# Arduino_keyboard_schematic.net
KiCad netlist of a schematic drawn in EAGLE
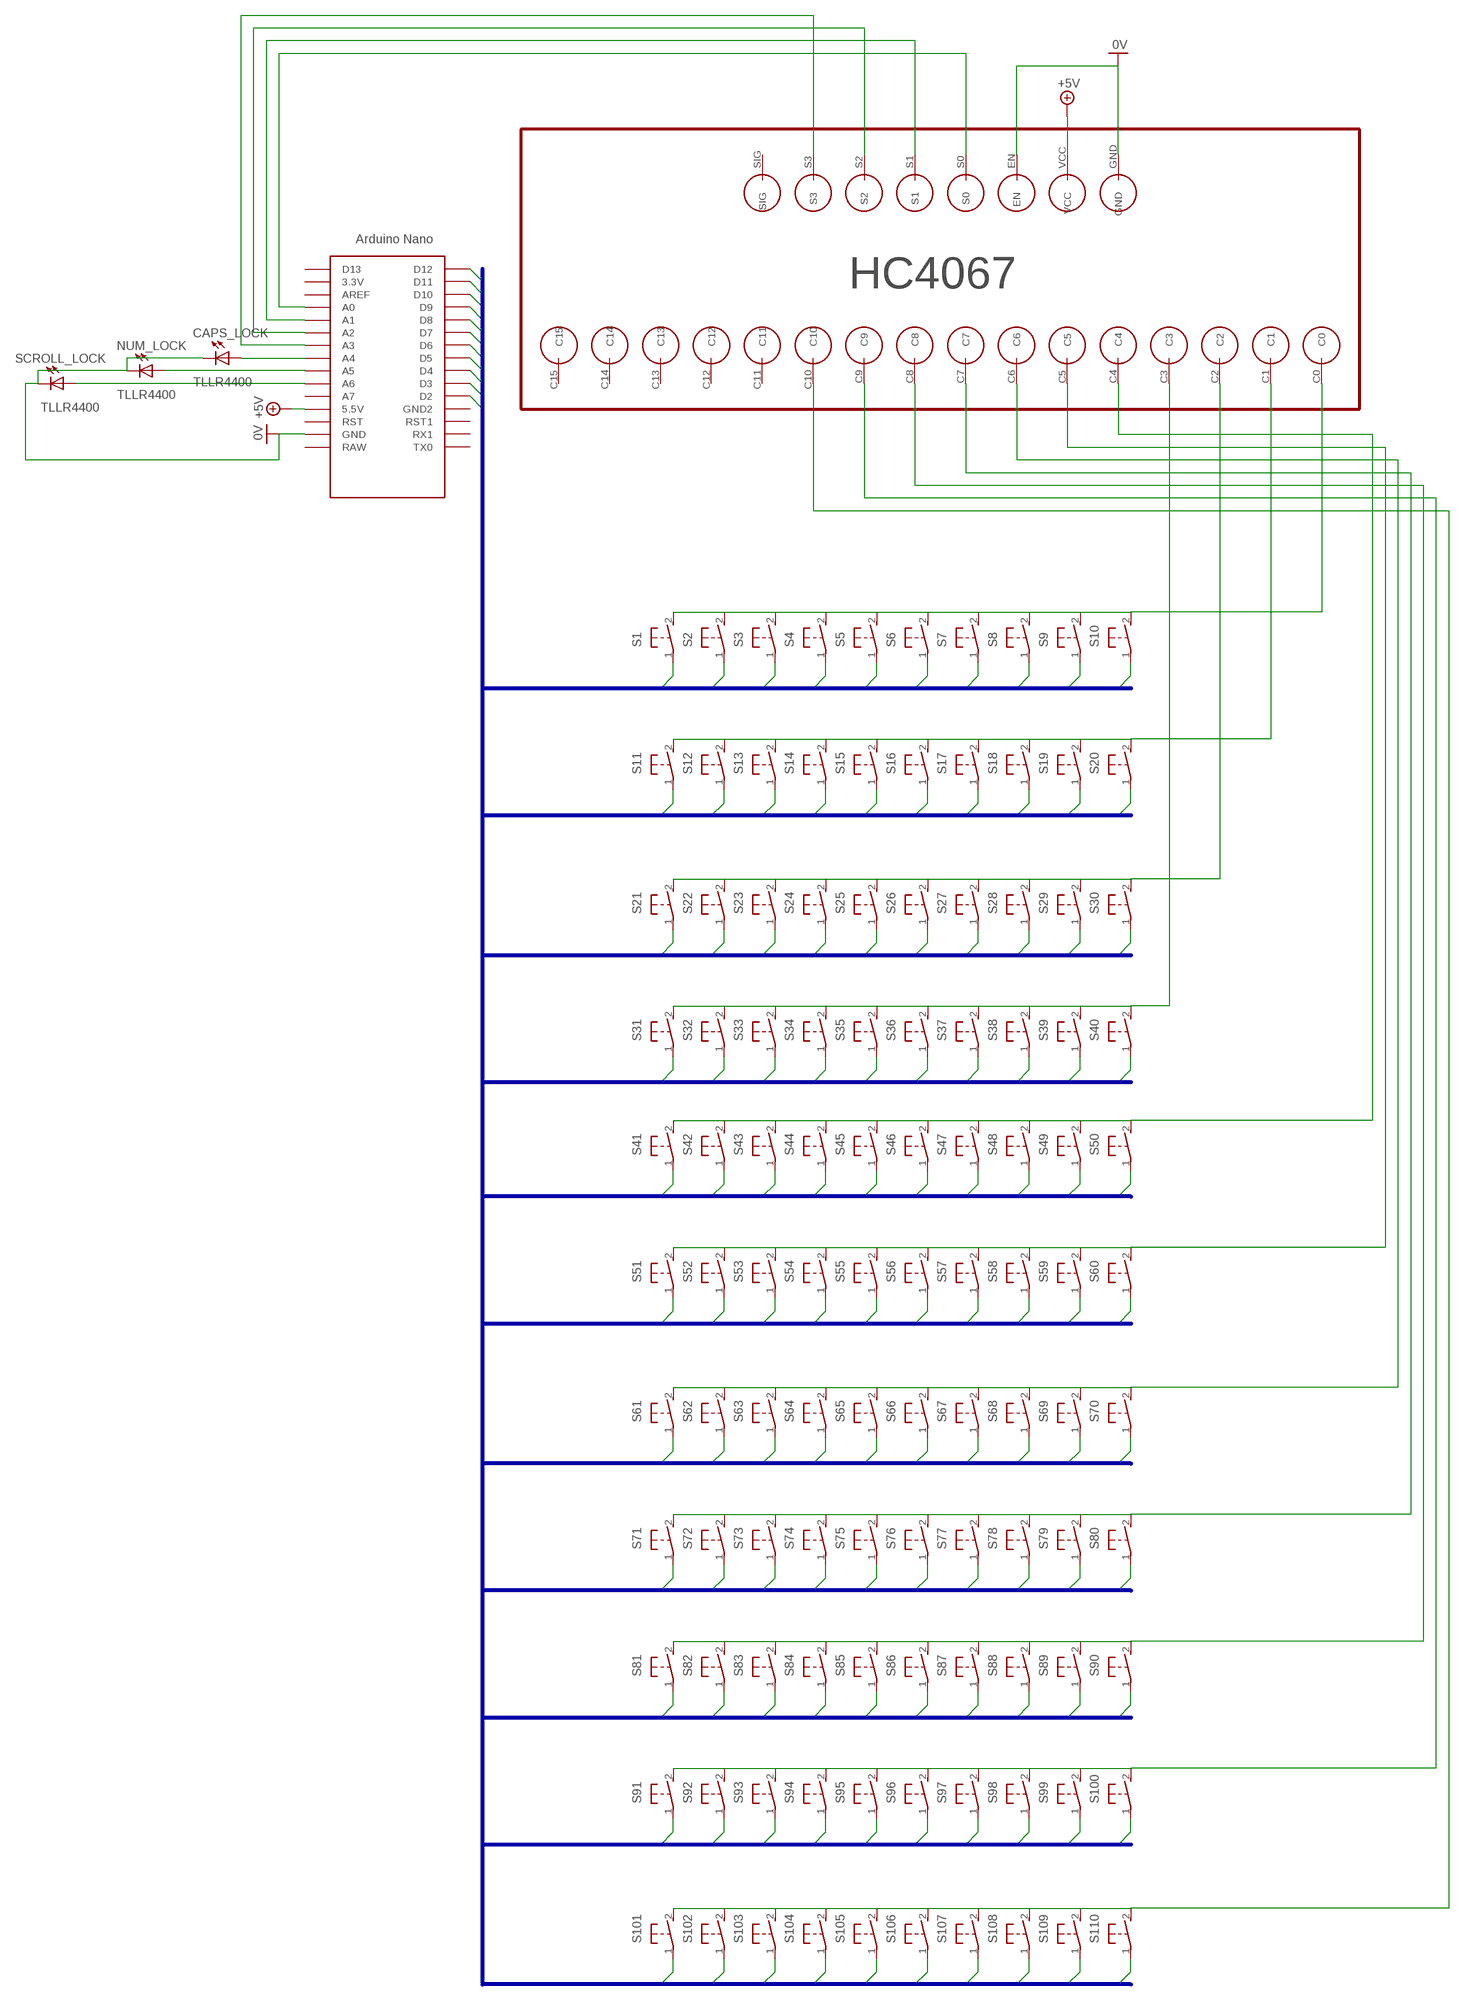
[diagram p0: schematic, sheet 1]

(export (version "E")
  (design (tool "Eeschema 10.0.6"))
  (components
    (comp (ref "CAPS_LOCK")
      (value "TLLR4400")
      (footprint "eagle-import:LED3MM")
      (fields (field (name "MF") "VISHAY SEMICONDUCTOR"))
      (libsource (lib "eagle-import") (part "TLLR4400"))
    )
    (comp (ref "NUM_LOCK")
      (value "TLLR4400")
      (footprint "eagle-import:LED3MM")
      (fields (field (name "MF") "VISHAY SEMICONDUCTOR"))
      (libsource (lib "eagle-import") (part "TLLR4400"))
    )
    (comp (ref "S1")
      (value "31-XX")
      (footprint "eagle-import:B3F-31XX")
      (fields (field (name "MPN") "B3F-3100"))
      (libsource (lib "eagle-import") (part "31-XX"))
    )
    (comp (ref "S2")
      (value "31-XX")
      (footprint "eagle-import:B3F-31XX")
      (fields (field (name "MPN") "B3F-3100"))
      (libsource (lib "eagle-import") (part "31-XX"))
    )
    (comp (ref "S3")
      (value "31-XX")
      (footprint "eagle-import:B3F-31XX")
      (fields (field (name "MPN") "B3F-3100"))
      (libsource (lib "eagle-import") (part "31-XX"))
    )
    (comp (ref "S4")
      (value "31-XX")
      (footprint "eagle-import:B3F-31XX")
      (fields (field (name "MPN") "B3F-3100"))
      (libsource (lib "eagle-import") (part "31-XX"))
    )
    (comp (ref "S5")
      (value "31-XX")
      (footprint "eagle-import:B3F-31XX")
      (fields (field (name "MPN") "B3F-3100"))
      (libsource (lib "eagle-import") (part "31-XX"))
    )
    (comp (ref "S6")
      (value "31-XX")
      (footprint "eagle-import:B3F-31XX")
      (fields (field (name "MPN") "B3F-3100"))
      (libsource (lib "eagle-import") (part "31-XX"))
    )
    (comp (ref "S7")
      (value "31-XX")
      (footprint "eagle-import:B3F-31XX")
      (fields (field (name "MPN") "B3F-3100"))
      (libsource (lib "eagle-import") (part "31-XX"))
    )
    (comp (ref "S8")
      (value "31-XX")
      (footprint "eagle-import:B3F-31XX")
      (fields (field (name "MPN") "B3F-3100"))
      (libsource (lib "eagle-import") (part "31-XX"))
    )
    (comp (ref "S9")
      (value "31-XX")
      (footprint "eagle-import:B3F-31XX")
      (fields (field (name "MPN") "B3F-3100"))
      (libsource (lib "eagle-import") (part "31-XX"))
    )
    (comp (ref "S10")
      (value "31-XX")
      (footprint "eagle-import:B3F-31XX")
      (fields (field (name "MPN") "B3F-3100"))
      (libsource (lib "eagle-import") (part "31-XX"))
    )
    (comp (ref "S11")
      (value "31-XX")
      (footprint "eagle-import:B3F-31XX")
      (fields (field (name "MPN") "B3F-3100"))
      (libsource (lib "eagle-import") (part "31-XX"))
    )
    (comp (ref "S12")
      (value "31-XX")
      (footprint "eagle-import:B3F-31XX")
      (fields (field (name "MPN") "B3F-3100"))
      (libsource (lib "eagle-import") (part "31-XX"))
    )
    (comp (ref "S13")
      (value "31-XX")
      (footprint "eagle-import:B3F-31XX")
      (fields (field (name "MPN") "B3F-3100"))
      (libsource (lib "eagle-import") (part "31-XX"))
    )
    (comp (ref "S14")
      (value "31-XX")
      (footprint "eagle-import:B3F-31XX")
      (fields (field (name "MPN") "B3F-3100"))
      (libsource (lib "eagle-import") (part "31-XX"))
    )
    (comp (ref "S15")
      (value "31-XX")
      (footprint "eagle-import:B3F-31XX")
      (fields (field (name "MPN") "B3F-3100"))
      (libsource (lib "eagle-import") (part "31-XX"))
    )
    (comp (ref "S16")
      (value "31-XX")
      (footprint "eagle-import:B3F-31XX")
      (fields (field (name "MPN") "B3F-3100"))
      (libsource (lib "eagle-import") (part "31-XX"))
    )
    (comp (ref "S17")
      (value "31-XX")
      (footprint "eagle-import:B3F-31XX")
      (fields (field (name "MPN") "B3F-3100"))
      (libsource (lib "eagle-import") (part "31-XX"))
    )
    (comp (ref "S18")
      (value "31-XX")
      (footprint "eagle-import:B3F-31XX")
      (fields (field (name "MPN") "B3F-3100"))
      (libsource (lib "eagle-import") (part "31-XX"))
    )
    (comp (ref "S19")
      (value "31-XX")
      (footprint "eagle-import:B3F-31XX")
      (fields (field (name "MPN") "B3F-3100"))
      (libsource (lib "eagle-import") (part "31-XX"))
    )
    (comp (ref "S20")
      (value "31-XX")
      (footprint "eagle-import:B3F-31XX")
      (fields (field (name "MPN") "B3F-3100"))
      (libsource (lib "eagle-import") (part "31-XX"))
    )
    (comp (ref "S21")
      (value "31-XX")
      (footprint "eagle-import:B3F-31XX")
      (fields (field (name "MPN") "B3F-3100"))
      (libsource (lib "eagle-import") (part "31-XX"))
    )
    (comp (ref "S22")
      (value "31-XX")
      (footprint "eagle-import:B3F-31XX")
      (fields (field (name "MPN") "B3F-3100"))
      (libsource (lib "eagle-import") (part "31-XX"))
    )
    (comp (ref "S23")
      (value "31-XX")
      (footprint "eagle-import:B3F-31XX")
      (fields (field (name "MPN") "B3F-3100"))
      (libsource (lib "eagle-import") (part "31-XX"))
    )
    (comp (ref "S24")
      (value "31-XX")
      (footprint "eagle-import:B3F-31XX")
      (fields (field (name "MPN") "B3F-3100"))
      (libsource (lib "eagle-import") (part "31-XX"))
    )
    (comp (ref "S25")
      (value "31-XX")
      (footprint "eagle-import:B3F-31XX")
      (fields (field (name "MPN") "B3F-3100"))
      (libsource (lib "eagle-import") (part "31-XX"))
    )
    (comp (ref "S26")
      (value "31-XX")
      (footprint "eagle-import:B3F-31XX")
      (fields (field (name "MPN") "B3F-3100"))
      (libsource (lib "eagle-import") (part "31-XX"))
    )
    (comp (ref "S27")
      (value "31-XX")
      (footprint "eagle-import:B3F-31XX")
      (fields (field (name "MPN") "B3F-3100"))
      (libsource (lib "eagle-import") (part "31-XX"))
    )
    (comp (ref "S28")
      (value "31-XX")
      (footprint "eagle-import:B3F-31XX")
      (fields (field (name "MPN") "B3F-3100"))
      (libsource (lib "eagle-import") (part "31-XX"))
    )
    (comp (ref "S29")
      (value "31-XX")
      (footprint "eagle-import:B3F-31XX")
      (fields (field (name "MPN") "B3F-3100"))
      (libsource (lib "eagle-import") (part "31-XX"))
    )
    (comp (ref "S30")
      (value "31-XX")
      (footprint "eagle-import:B3F-31XX")
      (fields (field (name "MPN") "B3F-3100"))
      (libsource (lib "eagle-import") (part "31-XX"))
    )
    (comp (ref "S31")
      (value "31-XX")
      (footprint "eagle-import:B3F-31XX")
      (fields (field (name "MPN") "B3F-3100"))
      (libsource (lib "eagle-import") (part "31-XX"))
    )
    (comp (ref "S32")
      (value "31-XX")
      (footprint "eagle-import:B3F-31XX")
      (fields (field (name "MPN") "B3F-3100"))
      (libsource (lib "eagle-import") (part "31-XX"))
    )
    (comp (ref "S33")
      (value "31-XX")
      (footprint "eagle-import:B3F-31XX")
      (fields (field (name "MPN") "B3F-3100"))
      (libsource (lib "eagle-import") (part "31-XX"))
    )
    (comp (ref "S34")
      (value "31-XX")
      (footprint "eagle-import:B3F-31XX")
      (fields (field (name "MPN") "B3F-3100"))
      (libsource (lib "eagle-import") (part "31-XX"))
    )
    (comp (ref "S35")
      (value "31-XX")
      (footprint "eagle-import:B3F-31XX")
      (fields (field (name "MPN") "B3F-3100"))
      (libsource (lib "eagle-import") (part "31-XX"))
    )
    (comp (ref "S36")
      (value "31-XX")
      (footprint "eagle-import:B3F-31XX")
      (fields (field (name "MPN") "B3F-3100"))
      (libsource (lib "eagle-import") (part "31-XX"))
    )
    (comp (ref "S37")
      (value "31-XX")
      (footprint "eagle-import:B3F-31XX")
      (fields (field (name "MPN") "B3F-3100"))
      (libsource (lib "eagle-import") (part "31-XX"))
    )
    (comp (ref "S38")
      (value "31-XX")
      (footprint "eagle-import:B3F-31XX")
      (fields (field (name "MPN") "B3F-3100"))
      (libsource (lib "eagle-import") (part "31-XX"))
    )
    (comp (ref "S39")
      (value "31-XX")
      (footprint "eagle-import:B3F-31XX")
      (fields (field (name "MPN") "B3F-3100"))
      (libsource (lib "eagle-import") (part "31-XX"))
    )
    (comp (ref "S40")
      (value "31-XX")
      (footprint "eagle-import:B3F-31XX")
      (fields (field (name "MPN") "B3F-3100"))
      (libsource (lib "eagle-import") (part "31-XX"))
    )
    (comp (ref "S41")
      (value "31-XX")
      (footprint "eagle-import:B3F-31XX")
      (fields (field (name "MPN") "B3F-3100"))
      (libsource (lib "eagle-import") (part "31-XX"))
    )
    (comp (ref "S42")
      (value "31-XX")
      (footprint "eagle-import:B3F-31XX")
      (fields (field (name "MPN") "B3F-3100"))
      (libsource (lib "eagle-import") (part "31-XX"))
    )
    (comp (ref "S43")
      (value "31-XX")
      (footprint "eagle-import:B3F-31XX")
      (fields (field (name "MPN") "B3F-3100"))
      (libsource (lib "eagle-import") (part "31-XX"))
    )
    (comp (ref "S44")
      (value "31-XX")
      (footprint "eagle-import:B3F-31XX")
      (fields (field (name "MPN") "B3F-3100"))
      (libsource (lib "eagle-import") (part "31-XX"))
    )
    (comp (ref "S45")
      (value "31-XX")
      (footprint "eagle-import:B3F-31XX")
      (fields (field (name "MPN") "B3F-3100"))
      (libsource (lib "eagle-import") (part "31-XX"))
    )
    (comp (ref "S46")
      (value "31-XX")
      (footprint "eagle-import:B3F-31XX")
      (fields (field (name "MPN") "B3F-3100"))
      (libsource (lib "eagle-import") (part "31-XX"))
    )
    (comp (ref "S47")
      (value "31-XX")
      (footprint "eagle-import:B3F-31XX")
      (fields (field (name "MPN") "B3F-3100"))
      (libsource (lib "eagle-import") (part "31-XX"))
    )
    (comp (ref "S48")
      (value "31-XX")
      (footprint "eagle-import:B3F-31XX")
      (fields (field (name "MPN") "B3F-3100"))
      (libsource (lib "eagle-import") (part "31-XX"))
    )
    (comp (ref "S49")
      (value "31-XX")
      (footprint "eagle-import:B3F-31XX")
      (fields (field (name "MPN") "B3F-3100"))
      (libsource (lib "eagle-import") (part "31-XX"))
    )
    (comp (ref "S50")
      (value "31-XX")
      (footprint "eagle-import:B3F-31XX")
      (fields (field (name "MPN") "B3F-3100"))
      (libsource (lib "eagle-import") (part "31-XX"))
    )
    (comp (ref "S51")
      (value "31-XX")
      (footprint "eagle-import:B3F-31XX")
      (fields (field (name "MPN") "B3F-3100"))
      (libsource (lib "eagle-import") (part "31-XX"))
    )
    (comp (ref "S52")
      (value "31-XX")
      (footprint "eagle-import:B3F-31XX")
      (fields (field (name "MPN") "B3F-3100"))
      (libsource (lib "eagle-import") (part "31-XX"))
    )
    (comp (ref "S53")
      (value "31-XX")
      (footprint "eagle-import:B3F-31XX")
      (fields (field (name "MPN") "B3F-3100"))
      (libsource (lib "eagle-import") (part "31-XX"))
    )
    (comp (ref "S54")
      (value "31-XX")
      (footprint "eagle-import:B3F-31XX")
      (fields (field (name "MPN") "B3F-3100"))
      (libsource (lib "eagle-import") (part "31-XX"))
    )
    (comp (ref "S55")
      (value "31-XX")
      (footprint "eagle-import:B3F-31XX")
      (fields (field (name "MPN") "B3F-3100"))
      (libsource (lib "eagle-import") (part "31-XX"))
    )
    (comp (ref "S56")
      (value "31-XX")
      (footprint "eagle-import:B3F-31XX")
      (fields (field (name "MPN") "B3F-3100"))
      (libsource (lib "eagle-import") (part "31-XX"))
    )
    (comp (ref "S57")
      (value "31-XX")
      (footprint "eagle-import:B3F-31XX")
      (fields (field (name "MPN") "B3F-3100"))
      (libsource (lib "eagle-import") (part "31-XX"))
    )
    (comp (ref "S58")
      (value "31-XX")
      (footprint "eagle-import:B3F-31XX")
      (fields (field (name "MPN") "B3F-3100"))
      (libsource (lib "eagle-import") (part "31-XX"))
    )
    (comp (ref "S59")
      (value "31-XX")
      (footprint "eagle-import:B3F-31XX")
      (fields (field (name "MPN") "B3F-3100"))
      (libsource (lib "eagle-import") (part "31-XX"))
    )
    (comp (ref "S60")
      (value "31-XX")
      (footprint "eagle-import:B3F-31XX")
      (fields (field (name "MPN") "B3F-3100"))
      (libsource (lib "eagle-import") (part "31-XX"))
    )
    (comp (ref "S61")
      (value "31-XX")
      (footprint "eagle-import:B3F-31XX")
      (fields (field (name "MPN") "B3F-3100"))
      (libsource (lib "eagle-import") (part "31-XX"))
    )
    (comp (ref "S62")
      (value "31-XX")
      (footprint "eagle-import:B3F-31XX")
      (fields (field (name "MPN") "B3F-3100"))
      (libsource (lib "eagle-import") (part "31-XX"))
    )
    (comp (ref "S63")
      (value "31-XX")
      (footprint "eagle-import:B3F-31XX")
      (fields (field (name "MPN") "B3F-3100"))
      (libsource (lib "eagle-import") (part "31-XX"))
    )
    (comp (ref "S64")
      (value "31-XX")
      (footprint "eagle-import:B3F-31XX")
      (fields (field (name "MPN") "B3F-3100"))
      (libsource (lib "eagle-import") (part "31-XX"))
    )
    (comp (ref "S65")
      (value "31-XX")
      (footprint "eagle-import:B3F-31XX")
      (fields (field (name "MPN") "B3F-3100"))
      (libsource (lib "eagle-import") (part "31-XX"))
    )
    (comp (ref "S66")
      (value "31-XX")
      (footprint "eagle-import:B3F-31XX")
      (fields (field (name "MPN") "B3F-3100"))
      (libsource (lib "eagle-import") (part "31-XX"))
    )
    (comp (ref "S67")
      (value "31-XX")
      (footprint "eagle-import:B3F-31XX")
      (fields (field (name "MPN") "B3F-3100"))
      (libsource (lib "eagle-import") (part "31-XX"))
    )
    (comp (ref "S68")
      (value "31-XX")
      (footprint "eagle-import:B3F-31XX")
      (fields (field (name "MPN") "B3F-3100"))
      (libsource (lib "eagle-import") (part "31-XX"))
    )
    (comp (ref "S69")
      (value "31-XX")
      (footprint "eagle-import:B3F-31XX")
      (fields (field (name "MPN") "B3F-3100"))
      (libsource (lib "eagle-import") (part "31-XX"))
    )
    (comp (ref "S70")
      (value "31-XX")
      (footprint "eagle-import:B3F-31XX")
      (fields (field (name "MPN") "B3F-3100"))
      (libsource (lib "eagle-import") (part "31-XX"))
    )
    (comp (ref "S71")
      (value "31-XX")
      (footprint "eagle-import:B3F-31XX")
      (fields (field (name "MPN") "B3F-3100"))
      (libsource (lib "eagle-import") (part "31-XX"))
    )
    (comp (ref "S72")
      (value "31-XX")
      (footprint "eagle-import:B3F-31XX")
      (fields (field (name "MPN") "B3F-3100"))
      (libsource (lib "eagle-import") (part "31-XX"))
    )
    (comp (ref "S73")
      (value "31-XX")
      (footprint "eagle-import:B3F-31XX")
      (fields (field (name "MPN") "B3F-3100"))
      (libsource (lib "eagle-import") (part "31-XX"))
    )
    (comp (ref "S74")
      (value "31-XX")
      (footprint "eagle-import:B3F-31XX")
      (fields (field (name "MPN") "B3F-3100"))
      (libsource (lib "eagle-import") (part "31-XX"))
    )
    (comp (ref "S75")
      (value "31-XX")
      (footprint "eagle-import:B3F-31XX")
      (fields (field (name "MPN") "B3F-3100"))
      (libsource (lib "eagle-import") (part "31-XX"))
    )
    (comp (ref "S76")
      (value "31-XX")
      (footprint "eagle-import:B3F-31XX")
      (fields (field (name "MPN") "B3F-3100"))
      (libsource (lib "eagle-import") (part "31-XX"))
    )
    (comp (ref "S77")
      (value "31-XX")
      (footprint "eagle-import:B3F-31XX")
      (fields (field (name "MPN") "B3F-3100"))
      (libsource (lib "eagle-import") (part "31-XX"))
    )
    (comp (ref "S78")
      (value "31-XX")
      (footprint "eagle-import:B3F-31XX")
      (fields (field (name "MPN") "B3F-3100"))
      (libsource (lib "eagle-import") (part "31-XX"))
    )
    (comp (ref "S79")
      (value "31-XX")
      (footprint "eagle-import:B3F-31XX")
      (fields (field (name "MPN") "B3F-3100"))
      (libsource (lib "eagle-import") (part "31-XX"))
    )
    (comp (ref "S80")
      (value "31-XX")
      (footprint "eagle-import:B3F-31XX")
      (fields (field (name "MPN") "B3F-3100"))
      (libsource (lib "eagle-import") (part "31-XX"))
    )
    (comp (ref "S81")
      (value "31-XX")
      (footprint "eagle-import:B3F-31XX")
      (fields (field (name "MPN") "B3F-3100"))
      (libsource (lib "eagle-import") (part "31-XX"))
    )
    (comp (ref "S82")
      (value "31-XX")
      (footprint "eagle-import:B3F-31XX")
      (fields (field (name "MPN") "B3F-3100"))
      (libsource (lib "eagle-import") (part "31-XX"))
    )
    (comp (ref "S83")
      (value "31-XX")
      (footprint "eagle-import:B3F-31XX")
      (fields (field (name "MPN") "B3F-3100"))
      (libsource (lib "eagle-import") (part "31-XX"))
    )
    (comp (ref "S84")
      (value "31-XX")
      (footprint "eagle-import:B3F-31XX")
      (fields (field (name "MPN") "B3F-3100"))
      (libsource (lib "eagle-import") (part "31-XX"))
    )
    (comp (ref "S85")
      (value "31-XX")
      (footprint "eagle-import:B3F-31XX")
      (fields (field (name "MPN") "B3F-3100"))
      (libsource (lib "eagle-import") (part "31-XX"))
    )
    (comp (ref "S86")
      (value "31-XX")
      (footprint "eagle-import:B3F-31XX")
      (fields (field (name "MPN") "B3F-3100"))
      (libsource (lib "eagle-import") (part "31-XX"))
    )
    (comp (ref "S87")
      (value "31-XX")
      (footprint "eagle-import:B3F-31XX")
      (fields (field (name "MPN") "B3F-3100"))
      (libsource (lib "eagle-import") (part "31-XX"))
    )
    (comp (ref "S88")
      (value "31-XX")
      (footprint "eagle-import:B3F-31XX")
      (fields (field (name "MPN") "B3F-3100"))
      (libsource (lib "eagle-import") (part "31-XX"))
    )
    (comp (ref "S89")
      (value "31-XX")
      (footprint "eagle-import:B3F-31XX")
      (fields (field (name "MPN") "B3F-3100"))
      (libsource (lib "eagle-import") (part "31-XX"))
    )
    (comp (ref "S90")
      (value "31-XX")
      (footprint "eagle-import:B3F-31XX")
      (fields (field (name "MPN") "B3F-3100"))
      (libsource (lib "eagle-import") (part "31-XX"))
    )
    (comp (ref "S91")
      (value "31-XX")
      (footprint "eagle-import:B3F-31XX")
      (fields (field (name "MPN") "B3F-3100"))
      (libsource (lib "eagle-import") (part "31-XX"))
    )
    (comp (ref "S92")
      (value "31-XX")
      (footprint "eagle-import:B3F-31XX")
      (fields (field (name "MPN") "B3F-3100"))
      (libsource (lib "eagle-import") (part "31-XX"))
    )
    (comp (ref "S93")
      (value "31-XX")
      (footprint "eagle-import:B3F-31XX")
      (fields (field (name "MPN") "B3F-3100"))
      (libsource (lib "eagle-import") (part "31-XX"))
    )
    (comp (ref "S94")
      (value "31-XX")
      (footprint "eagle-import:B3F-31XX")
      (fields (field (name "MPN") "B3F-3100"))
      (libsource (lib "eagle-import") (part "31-XX"))
    )
    (comp (ref "S95")
      (value "31-XX")
      (footprint "eagle-import:B3F-31XX")
      (fields (field (name "MPN") "B3F-3100"))
      (libsource (lib "eagle-import") (part "31-XX"))
    )
    (comp (ref "S96")
      (value "31-XX")
      (footprint "eagle-import:B3F-31XX")
      (fields (field (name "MPN") "B3F-3100"))
      (libsource (lib "eagle-import") (part "31-XX"))
    )
    (comp (ref "S97")
      (value "31-XX")
      (footprint "eagle-import:B3F-31XX")
      (fields (field (name "MPN") "B3F-3100"))
      (libsource (lib "eagle-import") (part "31-XX"))
    )
    (comp (ref "S98")
      (value "31-XX")
      (footprint "eagle-import:B3F-31XX")
      (fields (field (name "MPN") "B3F-3100"))
      (libsource (lib "eagle-import") (part "31-XX"))
    )
    (comp (ref "S99")
      (value "31-XX")
      (footprint "eagle-import:B3F-31XX")
      (fields (field (name "MPN") "B3F-3100"))
      (libsource (lib "eagle-import") (part "31-XX"))
    )
    (comp (ref "S100")
      (value "31-XX")
      (footprint "eagle-import:B3F-31XX")
      (fields (field (name "MPN") "B3F-3100"))
      (libsource (lib "eagle-import") (part "31-XX"))
    )
    (comp (ref "S101")
      (value "31-XX")
      (footprint "eagle-import:B3F-31XX")
      (fields (field (name "MPN") "B3F-3100"))
      (libsource (lib "eagle-import") (part "31-XX"))
    )
    (comp (ref "S102")
      (value "31-XX")
      (footprint "eagle-import:B3F-31XX")
      (fields (field (name "MPN") "B3F-3100"))
      (libsource (lib "eagle-import") (part "31-XX"))
    )
    (comp (ref "S103")
      (value "31-XX")
      (footprint "eagle-import:B3F-31XX")
      (fields (field (name "MPN") "B3F-3100"))
      (libsource (lib "eagle-import") (part "31-XX"))
    )
    (comp (ref "S104")
      (value "31-XX")
      (footprint "eagle-import:B3F-31XX")
      (fields (field (name "MPN") "B3F-3100"))
      (libsource (lib "eagle-import") (part "31-XX"))
    )
    (comp (ref "S105")
      (value "31-XX")
      (footprint "eagle-import:B3F-31XX")
      (fields (field (name "MPN") "B3F-3100"))
      (libsource (lib "eagle-import") (part "31-XX"))
    )
    (comp (ref "S106")
      (value "31-XX")
      (footprint "eagle-import:B3F-31XX")
      (fields (field (name "MPN") "B3F-3100"))
      (libsource (lib "eagle-import") (part "31-XX"))
    )
    (comp (ref "S107")
      (value "31-XX")
      (footprint "eagle-import:B3F-31XX")
      (fields (field (name "MPN") "B3F-3100"))
      (libsource (lib "eagle-import") (part "31-XX"))
    )
    (comp (ref "S108")
      (value "31-XX")
      (footprint "eagle-import:B3F-31XX")
      (fields (field (name "MPN") "B3F-3100"))
      (libsource (lib "eagle-import") (part "31-XX"))
    )
    (comp (ref "S109")
      (value "31-XX")
      (footprint "eagle-import:B3F-31XX")
      (fields (field (name "MPN") "B3F-3100"))
      (libsource (lib "eagle-import") (part "31-XX"))
    )
    (comp (ref "S110")
      (value "31-XX")
      (footprint "eagle-import:B3F-31XX")
      (fields (field (name "MPN") "B3F-3100"))
      (libsource (lib "eagle-import") (part "31-XX"))
    )
    (comp (ref "SCROLL_LOCK")
      (value "TLLR4400")
      (footprint "eagle-import:LED3MM")
      (fields (field (name "MF") "VISHAY SEMICONDUCTOR"))
      (libsource (lib "eagle-import") (part "TLLR4400"))
    )
    (comp (ref "U$1")
      (value "NANO")
      (footprint "eagle-import:NANO")
      (libsource (lib "eagle-import") (part "NANO"))
    )
    (comp (ref "U$2")
      (value "HC4067_BREAKOUT_BOARD")
      (footprint "eagle-import:ANALOG_MUX_BREAKOUT_HC4067")
      (libsource (lib "eagle-import") (part "HC4067_BREAKOUT_BOARD"))
    )
  )
  (nets
    (net (code "1") (name "+5V") (class "Default")
      (node (ref "U$1") (pin "5V") (pinfunction "5.5V_5V") (pintype "bidirectional"))
      (node (ref "U$2") (pin "VCC") (pinfunction "VCC_VCC") (pintype "bidirectional"))
    )
    (net (code "2") (name "/D_IN0") (class "Default")
      (node (ref "S1") (pin "1") (pinfunction "P_1") (pintype "passive"))
      (node (ref "S101") (pin "1") (pinfunction "P_1") (pintype "passive"))
      (node (ref "S11") (pin "1") (pinfunction "P_1") (pintype "passive"))
      (node (ref "S21") (pin "1") (pinfunction "P_1") (pintype "passive"))
      (node (ref "S31") (pin "1") (pinfunction "P_1") (pintype "passive"))
      (node (ref "S41") (pin "1") (pinfunction "P_1") (pintype "passive"))
      (node (ref "S51") (pin "1") (pinfunction "P_1") (pintype "passive"))
      (node (ref "S61") (pin "1") (pinfunction "P_1") (pintype "passive"))
      (node (ref "S71") (pin "1") (pinfunction "P_1") (pintype "passive"))
      (node (ref "S81") (pin "1") (pinfunction "P_1") (pintype "passive"))
      (node (ref "S91") (pin "1") (pinfunction "P_1") (pintype "passive"))
      (node (ref "U$1") (pin "D2") (pinfunction "D2_D2") (pintype "bidirectional"))
    )
    (net (code "3") (name "/D_IN1") (class "Default")
      (node (ref "S102") (pin "1") (pinfunction "P_1") (pintype "passive"))
      (node (ref "S12") (pin "1") (pinfunction "P_1") (pintype "passive"))
      (node (ref "S2") (pin "1") (pinfunction "P_1") (pintype "passive"))
      (node (ref "S22") (pin "1") (pinfunction "P_1") (pintype "passive"))
      (node (ref "S32") (pin "1") (pinfunction "P_1") (pintype "passive"))
      (node (ref "S42") (pin "1") (pinfunction "P_1") (pintype "passive"))
      (node (ref "S52") (pin "1") (pinfunction "P_1") (pintype "passive"))
      (node (ref "S62") (pin "1") (pinfunction "P_1") (pintype "passive"))
      (node (ref "S72") (pin "1") (pinfunction "P_1") (pintype "passive"))
      (node (ref "S82") (pin "1") (pinfunction "P_1") (pintype "passive"))
      (node (ref "S92") (pin "1") (pinfunction "P_1") (pintype "passive"))
      (node (ref "U$1") (pin "D3") (pinfunction "D3_D3") (pintype "bidirectional"))
    )
    (net (code "4") (name "/D_IN2") (class "Default")
      (node (ref "S103") (pin "1") (pinfunction "P_1") (pintype "passive"))
      (node (ref "S13") (pin "1") (pinfunction "P_1") (pintype "passive"))
      (node (ref "S23") (pin "1") (pinfunction "P_1") (pintype "passive"))
      (node (ref "S3") (pin "1") (pinfunction "P_1") (pintype "passive"))
      (node (ref "S33") (pin "1") (pinfunction "P_1") (pintype "passive"))
      (node (ref "S43") (pin "1") (pinfunction "P_1") (pintype "passive"))
      (node (ref "S53") (pin "1") (pinfunction "P_1") (pintype "passive"))
      (node (ref "S63") (pin "1") (pinfunction "P_1") (pintype "passive"))
      (node (ref "S73") (pin "1") (pinfunction "P_1") (pintype "passive"))
      (node (ref "S83") (pin "1") (pinfunction "P_1") (pintype "passive"))
      (node (ref "S93") (pin "1") (pinfunction "P_1") (pintype "passive"))
      (node (ref "U$1") (pin "D4") (pinfunction "D4_D4") (pintype "bidirectional"))
    )
    (net (code "5") (name "/D_IN3") (class "Default")
      (node (ref "S104") (pin "1") (pinfunction "P_1") (pintype "passive"))
      (node (ref "S14") (pin "1") (pinfunction "P_1") (pintype "passive"))
      (node (ref "S24") (pin "1") (pinfunction "P_1") (pintype "passive"))
      (node (ref "S34") (pin "1") (pinfunction "P_1") (pintype "passive"))
      (node (ref "S4") (pin "1") (pinfunction "P_1") (pintype "passive"))
      (node (ref "S44") (pin "1") (pinfunction "P_1") (pintype "passive"))
      (node (ref "S54") (pin "1") (pinfunction "P_1") (pintype "passive"))
      (node (ref "S64") (pin "1") (pinfunction "P_1") (pintype "passive"))
      (node (ref "S74") (pin "1") (pinfunction "P_1") (pintype "passive"))
      (node (ref "S84") (pin "1") (pinfunction "P_1") (pintype "passive"))
      (node (ref "S94") (pin "1") (pinfunction "P_1") (pintype "passive"))
      (node (ref "U$1") (pin "D5") (pinfunction "D5_D5") (pintype "bidirectional"))
    )
    (net (code "6") (name "/D_IN4") (class "Default")
      (node (ref "S105") (pin "1") (pinfunction "P_1") (pintype "passive"))
      (node (ref "S15") (pin "1") (pinfunction "P_1") (pintype "passive"))
      (node (ref "S25") (pin "1") (pinfunction "P_1") (pintype "passive"))
      (node (ref "S35") (pin "1") (pinfunction "P_1") (pintype "passive"))
      (node (ref "S45") (pin "1") (pinfunction "P_1") (pintype "passive"))
      (node (ref "S5") (pin "1") (pinfunction "P_1") (pintype "passive"))
      (node (ref "S55") (pin "1") (pinfunction "P_1") (pintype "passive"))
      (node (ref "S65") (pin "1") (pinfunction "P_1") (pintype "passive"))
      (node (ref "S75") (pin "1") (pinfunction "P_1") (pintype "passive"))
      (node (ref "S85") (pin "1") (pinfunction "P_1") (pintype "passive"))
      (node (ref "S95") (pin "1") (pinfunction "P_1") (pintype "passive"))
      (node (ref "U$1") (pin "D6") (pinfunction "D6_D6") (pintype "bidirectional"))
    )
    (net (code "7") (name "/D_IN5") (class "Default")
      (node (ref "S106") (pin "1") (pinfunction "P_1") (pintype "passive"))
      (node (ref "S16") (pin "1") (pinfunction "P_1") (pintype "passive"))
      (node (ref "S26") (pin "1") (pinfunction "P_1") (pintype "passive"))
      (node (ref "S36") (pin "1") (pinfunction "P_1") (pintype "passive"))
      (node (ref "S46") (pin "1") (pinfunction "P_1") (pintype "passive"))
      (node (ref "S56") (pin "1") (pinfunction "P_1") (pintype "passive"))
      (node (ref "S6") (pin "1") (pinfunction "P_1") (pintype "passive"))
      (node (ref "S66") (pin "1") (pinfunction "P_1") (pintype "passive"))
      (node (ref "S76") (pin "1") (pinfunction "P_1") (pintype "passive"))
      (node (ref "S86") (pin "1") (pinfunction "P_1") (pintype "passive"))
      (node (ref "S96") (pin "1") (pinfunction "P_1") (pintype "passive"))
      (node (ref "U$1") (pin "D7") (pinfunction "D7_D7") (pintype "bidirectional"))
    )
    (net (code "8") (name "/D_IN6") (class "Default")
      (node (ref "S107") (pin "1") (pinfunction "P_1") (pintype "passive"))
      (node (ref "S17") (pin "1") (pinfunction "P_1") (pintype "passive"))
      (node (ref "S27") (pin "1") (pinfunction "P_1") (pintype "passive"))
      (node (ref "S37") (pin "1") (pinfunction "P_1") (pintype "passive"))
      (node (ref "S47") (pin "1") (pinfunction "P_1") (pintype "passive"))
      (node (ref "S57") (pin "1") (pinfunction "P_1") (pintype "passive"))
      (node (ref "S67") (pin "1") (pinfunction "P_1") (pintype "passive"))
      (node (ref "S7") (pin "1") (pinfunction "P_1") (pintype "passive"))
      (node (ref "S77") (pin "1") (pinfunction "P_1") (pintype "passive"))
      (node (ref "S87") (pin "1") (pinfunction "P_1") (pintype "passive"))
      (node (ref "S97") (pin "1") (pinfunction "P_1") (pintype "passive"))
      (node (ref "U$1") (pin "D8") (pinfunction "D8_D8") (pintype "bidirectional"))
      (node (ref "U$1") (pin "D9") (pinfunction "D9_D9") (pintype "bidirectional"))
    )
    (net (code "9") (name "/D_IN7") (class "Default")
      (node (ref "S108") (pin "1") (pinfunction "P_1") (pintype "passive"))
      (node (ref "S18") (pin "1") (pinfunction "P_1") (pintype "passive"))
      (node (ref "S28") (pin "1") (pinfunction "P_1") (pintype "passive"))
      (node (ref "S38") (pin "1") (pinfunction "P_1") (pintype "passive"))
      (node (ref "S48") (pin "1") (pinfunction "P_1") (pintype "passive"))
      (node (ref "S58") (pin "1") (pinfunction "P_1") (pintype "passive"))
      (node (ref "S68") (pin "1") (pinfunction "P_1") (pintype "passive"))
      (node (ref "S78") (pin "1") (pinfunction "P_1") (pintype "passive"))
      (node (ref "S8") (pin "1") (pinfunction "P_1") (pintype "passive"))
      (node (ref "S88") (pin "1") (pinfunction "P_1") (pintype "passive"))
      (node (ref "S98") (pin "1") (pinfunction "P_1") (pintype "passive"))
      (node (ref "U$1") (pin "D10") (pinfunction "D10_D10") (pintype "bidirectional"))
    )
    (net (code "10") (name "/D_IN8") (class "Default")
      (node (ref "S109") (pin "1") (pinfunction "P_1") (pintype "passive"))
      (node (ref "S19") (pin "1") (pinfunction "P_1") (pintype "passive"))
      (node (ref "S29") (pin "1") (pinfunction "P_1") (pintype "passive"))
      (node (ref "S39") (pin "1") (pinfunction "P_1") (pintype "passive"))
      (node (ref "S49") (pin "1") (pinfunction "P_1") (pintype "passive"))
      (node (ref "S59") (pin "1") (pinfunction "P_1") (pintype "passive"))
      (node (ref "S69") (pin "1") (pinfunction "P_1") (pintype "passive"))
      (node (ref "S79") (pin "1") (pinfunction "P_1") (pintype "passive"))
      (node (ref "S89") (pin "1") (pinfunction "P_1") (pintype "passive"))
      (node (ref "S9") (pin "1") (pinfunction "P_1") (pintype "passive"))
      (node (ref "S99") (pin "1") (pinfunction "P_1") (pintype "passive"))
      (node (ref "U$1") (pin "D11") (pinfunction "D11_D11") (pintype "bidirectional"))
    )
    (net (code "11") (name "/D_IN9") (class "Default")
      (node (ref "S10") (pin "1") (pinfunction "P_1") (pintype "passive"))
      (node (ref "S100") (pin "1") (pinfunction "P_1") (pintype "passive"))
      (node (ref "S110") (pin "1") (pinfunction "P_1") (pintype "passive"))
      (node (ref "S20") (pin "1") (pinfunction "P_1") (pintype "passive"))
      (node (ref "S30") (pin "1") (pinfunction "P_1") (pintype "passive"))
      (node (ref "S40") (pin "1") (pinfunction "P_1") (pintype "passive"))
      (node (ref "S50") (pin "1") (pinfunction "P_1") (pintype "passive"))
      (node (ref "S60") (pin "1") (pinfunction "P_1") (pintype "passive"))
      (node (ref "S70") (pin "1") (pinfunction "P_1") (pintype "passive"))
      (node (ref "S80") (pin "1") (pinfunction "P_1") (pintype "passive"))
      (node (ref "S90") (pin "1") (pinfunction "P_1") (pintype "passive"))
      (node (ref "U$1") (pin "D12") (pinfunction "D12_D12") (pintype "bidirectional"))
    )
    (net (code "12") (name "0V") (class "Default")
      (node (ref "CAPS_LOCK") (pin "K") (pinfunction "C_K") (pintype "passive"))
      (node (ref "NUM_LOCK") (pin "K") (pinfunction "C_K") (pintype "passive"))
      (node (ref "SCROLL_LOCK") (pin "K") (pinfunction "C_K") (pintype "passive"))
      (node (ref "U$1") (pin "GND") (pinfunction "GND_GND") (pintype "bidirectional"))
      (node (ref "U$2") (pin "EN") (pinfunction "EN_EN") (pintype "bidirectional"))
      (node (ref "U$2") (pin "GND") (pinfunction "GND_GND") (pintype "bidirectional"))
    )
    (net (code "13") (name "Net-(CAPS_LOCK-PadA)") (class "Default")
      (node (ref "CAPS_LOCK") (pin "A") (pinfunction "A_A") (pintype "passive"))
      (node (ref "U$1") (pin "A4") (pinfunction "A4_A4") (pintype "bidirectional"))
    )
    (net (code "14") (name "Net-(NUM_LOCK-PadA)") (class "Default")
      (node (ref "NUM_LOCK") (pin "A") (pinfunction "A_A") (pintype "passive"))
      (node (ref "U$1") (pin "A5") (pinfunction "A5_A5") (pintype "bidirectional"))
    )
    (net (code "15") (name "Net-(S1-S)") (class "Default")
      (node (ref "S1") (pin "2") (pinfunction "S_2") (pintype "passive"))
      (node (ref "S10") (pin "2") (pinfunction "S_2") (pintype "passive"))
      (node (ref "S2") (pin "2") (pinfunction "S_2") (pintype "passive"))
      (node (ref "S3") (pin "2") (pinfunction "S_2") (pintype "passive"))
      (node (ref "S4") (pin "2") (pinfunction "S_2") (pintype "passive"))
      (node (ref "S5") (pin "2") (pinfunction "S_2") (pintype "passive"))
      (node (ref "S6") (pin "2") (pinfunction "S_2") (pintype "passive"))
      (node (ref "S7") (pin "2") (pinfunction "S_2") (pintype "passive"))
      (node (ref "S8") (pin "2") (pinfunction "S_2") (pintype "passive"))
      (node (ref "S9") (pin "2") (pinfunction "S_2") (pintype "passive"))
      (node (ref "U$2") (pin "C0") (pinfunction "C0_C0") (pintype "bidirectional"))
    )
    (net (code "16") (name "Net-(S11-S)") (class "Default")
      (node (ref "S11") (pin "2") (pinfunction "S_2") (pintype "passive"))
      (node (ref "S12") (pin "2") (pinfunction "S_2") (pintype "passive"))
      (node (ref "S13") (pin "2") (pinfunction "S_2") (pintype "passive"))
      (node (ref "S14") (pin "2") (pinfunction "S_2") (pintype "passive"))
      (node (ref "S15") (pin "2") (pinfunction "S_2") (pintype "passive"))
      (node (ref "S16") (pin "2") (pinfunction "S_2") (pintype "passive"))
      (node (ref "S17") (pin "2") (pinfunction "S_2") (pintype "passive"))
      (node (ref "S18") (pin "2") (pinfunction "S_2") (pintype "passive"))
      (node (ref "S19") (pin "2") (pinfunction "S_2") (pintype "passive"))
      (node (ref "S20") (pin "2") (pinfunction "S_2") (pintype "passive"))
      (node (ref "U$2") (pin "C1") (pinfunction "C1_C1") (pintype "bidirectional"))
    )
    (net (code "17") (name "Net-(S21-S)") (class "Default")
      (node (ref "S21") (pin "2") (pinfunction "S_2") (pintype "passive"))
      (node (ref "S22") (pin "2") (pinfunction "S_2") (pintype "passive"))
      (node (ref "S23") (pin "2") (pinfunction "S_2") (pintype "passive"))
      (node (ref "S24") (pin "2") (pinfunction "S_2") (pintype "passive"))
      (node (ref "S25") (pin "2") (pinfunction "S_2") (pintype "passive"))
      (node (ref "S26") (pin "2") (pinfunction "S_2") (pintype "passive"))
      (node (ref "S27") (pin "2") (pinfunction "S_2") (pintype "passive"))
      (node (ref "S28") (pin "2") (pinfunction "S_2") (pintype "passive"))
      (node (ref "S29") (pin "2") (pinfunction "S_2") (pintype "passive"))
      (node (ref "S30") (pin "2") (pinfunction "S_2") (pintype "passive"))
      (node (ref "U$2") (pin "C2") (pinfunction "C2_C2") (pintype "bidirectional"))
    )
    (net (code "18") (name "Net-(S31-S)") (class "Default")
      (node (ref "S31") (pin "2") (pinfunction "S_2") (pintype "passive"))
      (node (ref "S32") (pin "2") (pinfunction "S_2") (pintype "passive"))
      (node (ref "S33") (pin "2") (pinfunction "S_2") (pintype "passive"))
      (node (ref "S34") (pin "2") (pinfunction "S_2") (pintype "passive"))
      (node (ref "S35") (pin "2") (pinfunction "S_2") (pintype "passive"))
      (node (ref "S36") (pin "2") (pinfunction "S_2") (pintype "passive"))
      (node (ref "S37") (pin "2") (pinfunction "S_2") (pintype "passive"))
      (node (ref "S38") (pin "2") (pinfunction "S_2") (pintype "passive"))
      (node (ref "S39") (pin "2") (pinfunction "S_2") (pintype "passive"))
      (node (ref "S40") (pin "2") (pinfunction "S_2") (pintype "passive"))
      (node (ref "U$2") (pin "C3") (pinfunction "C3_C3") (pintype "bidirectional"))
    )
    (net (code "19") (name "Net-(S41-S)") (class "Default")
      (node (ref "S41") (pin "2") (pinfunction "S_2") (pintype "passive"))
      (node (ref "S42") (pin "2") (pinfunction "S_2") (pintype "passive"))
      (node (ref "S43") (pin "2") (pinfunction "S_2") (pintype "passive"))
      (node (ref "S44") (pin "2") (pinfunction "S_2") (pintype "passive"))
      (node (ref "S45") (pin "2") (pinfunction "S_2") (pintype "passive"))
      (node (ref "S46") (pin "2") (pinfunction "S_2") (pintype "passive"))
      (node (ref "S47") (pin "2") (pinfunction "S_2") (pintype "passive"))
      (node (ref "S48") (pin "2") (pinfunction "S_2") (pintype "passive"))
      (node (ref "S49") (pin "2") (pinfunction "S_2") (pintype "passive"))
      (node (ref "S50") (pin "2") (pinfunction "S_2") (pintype "passive"))
      (node (ref "U$2") (pin "C4") (pinfunction "C4_C4") (pintype "bidirectional"))
    )
    (net (code "20") (name "Net-(S51-S)") (class "Default")
      (node (ref "S51") (pin "2") (pinfunction "S_2") (pintype "passive"))
      (node (ref "S52") (pin "2") (pinfunction "S_2") (pintype "passive"))
      (node (ref "S53") (pin "2") (pinfunction "S_2") (pintype "passive"))
      (node (ref "S54") (pin "2") (pinfunction "S_2") (pintype "passive"))
      (node (ref "S55") (pin "2") (pinfunction "S_2") (pintype "passive"))
      (node (ref "S56") (pin "2") (pinfunction "S_2") (pintype "passive"))
      (node (ref "S57") (pin "2") (pinfunction "S_2") (pintype "passive"))
      (node (ref "S58") (pin "2") (pinfunction "S_2") (pintype "passive"))
      (node (ref "S59") (pin "2") (pinfunction "S_2") (pintype "passive"))
      (node (ref "S60") (pin "2") (pinfunction "S_2") (pintype "passive"))
      (node (ref "U$2") (pin "C5") (pinfunction "C5_C5") (pintype "bidirectional"))
    )
    (net (code "21") (name "Net-(S61-S)") (class "Default")
      (node (ref "S61") (pin "2") (pinfunction "S_2") (pintype "passive"))
      (node (ref "S62") (pin "2") (pinfunction "S_2") (pintype "passive"))
      (node (ref "S63") (pin "2") (pinfunction "S_2") (pintype "passive"))
      (node (ref "S64") (pin "2") (pinfunction "S_2") (pintype "passive"))
      (node (ref "S65") (pin "2") (pinfunction "S_2") (pintype "passive"))
      (node (ref "S66") (pin "2") (pinfunction "S_2") (pintype "passive"))
      (node (ref "S67") (pin "2") (pinfunction "S_2") (pintype "passive"))
      (node (ref "S68") (pin "2") (pinfunction "S_2") (pintype "passive"))
      (node (ref "S69") (pin "2") (pinfunction "S_2") (pintype "passive"))
      (node (ref "S70") (pin "2") (pinfunction "S_2") (pintype "passive"))
      (node (ref "U$2") (pin "C6") (pinfunction "C6_C6") (pintype "bidirectional"))
    )
    (net (code "22") (name "Net-(S71-S)") (class "Default")
      (node (ref "S71") (pin "2") (pinfunction "S_2") (pintype "passive"))
      (node (ref "S72") (pin "2") (pinfunction "S_2") (pintype "passive"))
      (node (ref "S73") (pin "2") (pinfunction "S_2") (pintype "passive"))
      (node (ref "S74") (pin "2") (pinfunction "S_2") (pintype "passive"))
      (node (ref "S75") (pin "2") (pinfunction "S_2") (pintype "passive"))
      (node (ref "S76") (pin "2") (pinfunction "S_2") (pintype "passive"))
      (node (ref "S77") (pin "2") (pinfunction "S_2") (pintype "passive"))
      (node (ref "S78") (pin "2") (pinfunction "S_2") (pintype "passive"))
      (node (ref "S79") (pin "2") (pinfunction "S_2") (pintype "passive"))
      (node (ref "S80") (pin "2") (pinfunction "S_2") (pintype "passive"))
      (node (ref "U$2") (pin "C7") (pinfunction "C7_C7") (pintype "bidirectional"))
    )
    (net (code "23") (name "Net-(S81-S)") (class "Default")
      (node (ref "S81") (pin "2") (pinfunction "S_2") (pintype "passive"))
      (node (ref "S82") (pin "2") (pinfunction "S_2") (pintype "passive"))
      (node (ref "S83") (pin "2") (pinfunction "S_2") (pintype "passive"))
      (node (ref "S84") (pin "2") (pinfunction "S_2") (pintype "passive"))
      (node (ref "S85") (pin "2") (pinfunction "S_2") (pintype "passive"))
      (node (ref "S86") (pin "2") (pinfunction "S_2") (pintype "passive"))
      (node (ref "S87") (pin "2") (pinfunction "S_2") (pintype "passive"))
      (node (ref "S88") (pin "2") (pinfunction "S_2") (pintype "passive"))
      (node (ref "S89") (pin "2") (pinfunction "S_2") (pintype "passive"))
      (node (ref "S90") (pin "2") (pinfunction "S_2") (pintype "passive"))
      (node (ref "U$2") (pin "C8") (pinfunction "C8_C8") (pintype "bidirectional"))
    )
    (net (code "24") (name "Net-(S100-S)") (class "Default")
      (node (ref "S100") (pin "2") (pinfunction "S_2") (pintype "passive"))
      (node (ref "S91") (pin "2") (pinfunction "S_2") (pintype "passive"))
      (node (ref "S92") (pin "2") (pinfunction "S_2") (pintype "passive"))
      (node (ref "S93") (pin "2") (pinfunction "S_2") (pintype "passive"))
      (node (ref "S94") (pin "2") (pinfunction "S_2") (pintype "passive"))
      (node (ref "S95") (pin "2") (pinfunction "S_2") (pintype "passive"))
      (node (ref "S96") (pin "2") (pinfunction "S_2") (pintype "passive"))
      (node (ref "S97") (pin "2") (pinfunction "S_2") (pintype "passive"))
      (node (ref "S98") (pin "2") (pinfunction "S_2") (pintype "passive"))
      (node (ref "S99") (pin "2") (pinfunction "S_2") (pintype "passive"))
      (node (ref "U$2") (pin "C9") (pinfunction "C9_C9") (pintype "bidirectional"))
    )
    (net (code "25") (name "Net-(S101-S)") (class "Default")
      (node (ref "S101") (pin "2") (pinfunction "S_2") (pintype "passive"))
      (node (ref "S102") (pin "2") (pinfunction "S_2") (pintype "passive"))
      (node (ref "S103") (pin "2") (pinfunction "S_2") (pintype "passive"))
      (node (ref "S104") (pin "2") (pinfunction "S_2") (pintype "passive"))
      (node (ref "S105") (pin "2") (pinfunction "S_2") (pintype "passive"))
      (node (ref "S106") (pin "2") (pinfunction "S_2") (pintype "passive"))
      (node (ref "S107") (pin "2") (pinfunction "S_2") (pintype "passive"))
      (node (ref "S108") (pin "2") (pinfunction "S_2") (pintype "passive"))
      (node (ref "S109") (pin "2") (pinfunction "S_2") (pintype "passive"))
      (node (ref "S110") (pin "2") (pinfunction "S_2") (pintype "passive"))
      (node (ref "U$2") (pin "C10") (pinfunction "C10_C10") (pintype "bidirectional"))
    )
    (net (code "26") (name "Net-(SCROLL_LOCK-PadA)") (class "Default")
      (node (ref "SCROLL_LOCK") (pin "A") (pinfunction "A_A") (pintype "passive"))
      (node (ref "U$1") (pin "A6") (pinfunction "A6_A6") (pintype "bidirectional"))
    )
    (net (code "27") (name "Net-(U$1-PadA0)") (class "Default")
      (node (ref "U$1") (pin "A0") (pinfunction "A0_A0") (pintype "bidirectional"))
      (node (ref "U$2") (pin "S0") (pinfunction "S0_S0") (pintype "bidirectional"))
    )
    (net (code "28") (name "Net-(U$1-PadA1)") (class "Default")
      (node (ref "U$1") (pin "A1") (pinfunction "A1_A1") (pintype "bidirectional"))
      (node (ref "U$2") (pin "S1") (pinfunction "S1_S1") (pintype "bidirectional"))
    )
    (net (code "29") (name "Net-(U$1-PadA2)") (class "Default")
      (node (ref "U$1") (pin "A2") (pinfunction "A2_A2") (pintype "bidirectional"))
      (node (ref "U$2") (pin "S2") (pinfunction "S2_S2") (pintype "bidirectional"))
    )
    (net (code "30") (name "Net-(U$1-PadA3)") (class "Default")
      (node (ref "U$1") (pin "A3") (pinfunction "A3_A3") (pintype "bidirectional"))
      (node (ref "U$2") (pin "S3") (pinfunction "S3_S3") (pintype "bidirectional"))
    )
    (net (code "31") (name "unconnected-(U$1-GND2-PadGND1)") (class "Default")
      (node (ref "U$1") (pin "GND1") (pinfunction "GND2_GND1") (pintype "bidirectional"))
    )
    (net (code "32") (name "unconnected-(U$1-Pad3.3V)") (class "Default")
      (node (ref "U$1") (pin "3.3V") (pinfunction "3.3V_3.3V") (pintype "bidirectional"))
    )
    (net (code "33") (name "unconnected-(U$1-PadA7)") (class "Default")
      (node (ref "U$1") (pin "A7") (pinfunction "A7_A7") (pintype "bidirectional"))
    )
    (net (code "34") (name "unconnected-(U$1-PadAREF)") (class "Default")
      (node (ref "U$1") (pin "AREF") (pinfunction "AREF_AREF") (pintype "bidirectional"))
    )
    (net (code "35") (name "unconnected-(U$1-PadD13)") (class "Default")
      (node (ref "U$1") (pin "D13") (pinfunction "D13_D13") (pintype "bidirectional"))
    )
    (net (code "36") (name "unconnected-(U$1-PadICSP1)") (class "Default")
      (node (ref "U$1") (pin "ICSP1") (pinfunction "ICSP1_ICSP1") (pintype "bidirectional"))
    )
    (net (code "37") (name "unconnected-(U$1-PadICSP2)") (class "Default")
      (node (ref "U$1") (pin "ICSP2") (pinfunction "ICSP2_ICSP2") (pintype "bidirectional"))
    )
    (net (code "38") (name "unconnected-(U$1-PadICSP3)") (class "Default")
      (node (ref "U$1") (pin "ICSP3") (pinfunction "ICSP3_ICSP3") (pintype "bidirectional"))
    )
    (net (code "39") (name "unconnected-(U$1-PadICSP4)") (class "Default")
      (node (ref "U$1") (pin "ICSP4") (pinfunction "ICSP4_ICSP4") (pintype "bidirectional"))
    )
    (net (code "40") (name "unconnected-(U$1-PadICSP5)") (class "Default")
      (node (ref "U$1") (pin "ICSP5") (pinfunction "ICSP5_ICSP5") (pintype "bidirectional"))
    )
    (net (code "41") (name "unconnected-(U$1-PadICSP6)") (class "Default")
      (node (ref "U$1") (pin "ICSP6") (pinfunction "ICSP6_ICSP6") (pintype "bidirectional"))
    )
    (net (code "42") (name "unconnected-(U$1-PadRAW)") (class "Default")
      (node (ref "U$1") (pin "RAW") (pinfunction "RAW_RAW") (pintype "bidirectional"))
    )
    (net (code "43") (name "unconnected-(U$1-PadRST)") (class "Default")
      (node (ref "U$1") (pin "RST") (pinfunction "RST_RST") (pintype "bidirectional"))
    )
    (net (code "44") (name "unconnected-(U$1-PadRST1)") (class "Default")
      (node (ref "U$1") (pin "RST1") (pinfunction "RST1_RST1") (pintype "bidirectional"))
    )
    (net (code "45") (name "unconnected-(U$1-PadRX1)") (class "Default")
      (node (ref "U$1") (pin "RX1") (pinfunction "RX1_RX1") (pintype "bidirectional"))
    )
    (net (code "46") (name "unconnected-(U$1-PadTX0)") (class "Default")
      (node (ref "U$1") (pin "TX0") (pinfunction "TX0_TX0") (pintype "bidirectional"))
    )
    (net (code "47") (name "unconnected-(U$2-PadC11)") (class "Default")
      (node (ref "U$2") (pin "C11") (pinfunction "C11_C11") (pintype "bidirectional"))
    )
    (net (code "48") (name "unconnected-(U$2-PadC12)") (class "Default")
      (node (ref "U$2") (pin "C12") (pinfunction "C12_C12") (pintype "bidirectional"))
    )
    (net (code "49") (name "unconnected-(U$2-PadC13)") (class "Default")
      (node (ref "U$2") (pin "C13") (pinfunction "C13_C13") (pintype "bidirectional"))
    )
    (net (code "50") (name "unconnected-(U$2-PadC14)") (class "Default")
      (node (ref "U$2") (pin "C14") (pinfunction "C14_C14") (pintype "bidirectional"))
    )
    (net (code "51") (name "unconnected-(U$2-PadC15)") (class "Default")
      (node (ref "U$2") (pin "C15") (pinfunction "C15_C15") (pintype "bidirectional"))
    )
    (net (code "52") (name "unconnected-(U$2-PadSIG)") (class "Default")
      (node (ref "U$2") (pin "SIG") (pinfunction "SIG_SIG") (pintype "bidirectional"))
    )
  )
)
